# P09_F28379D-IO2.net
KiCad netlist of a schematic drawn in Altium Designer
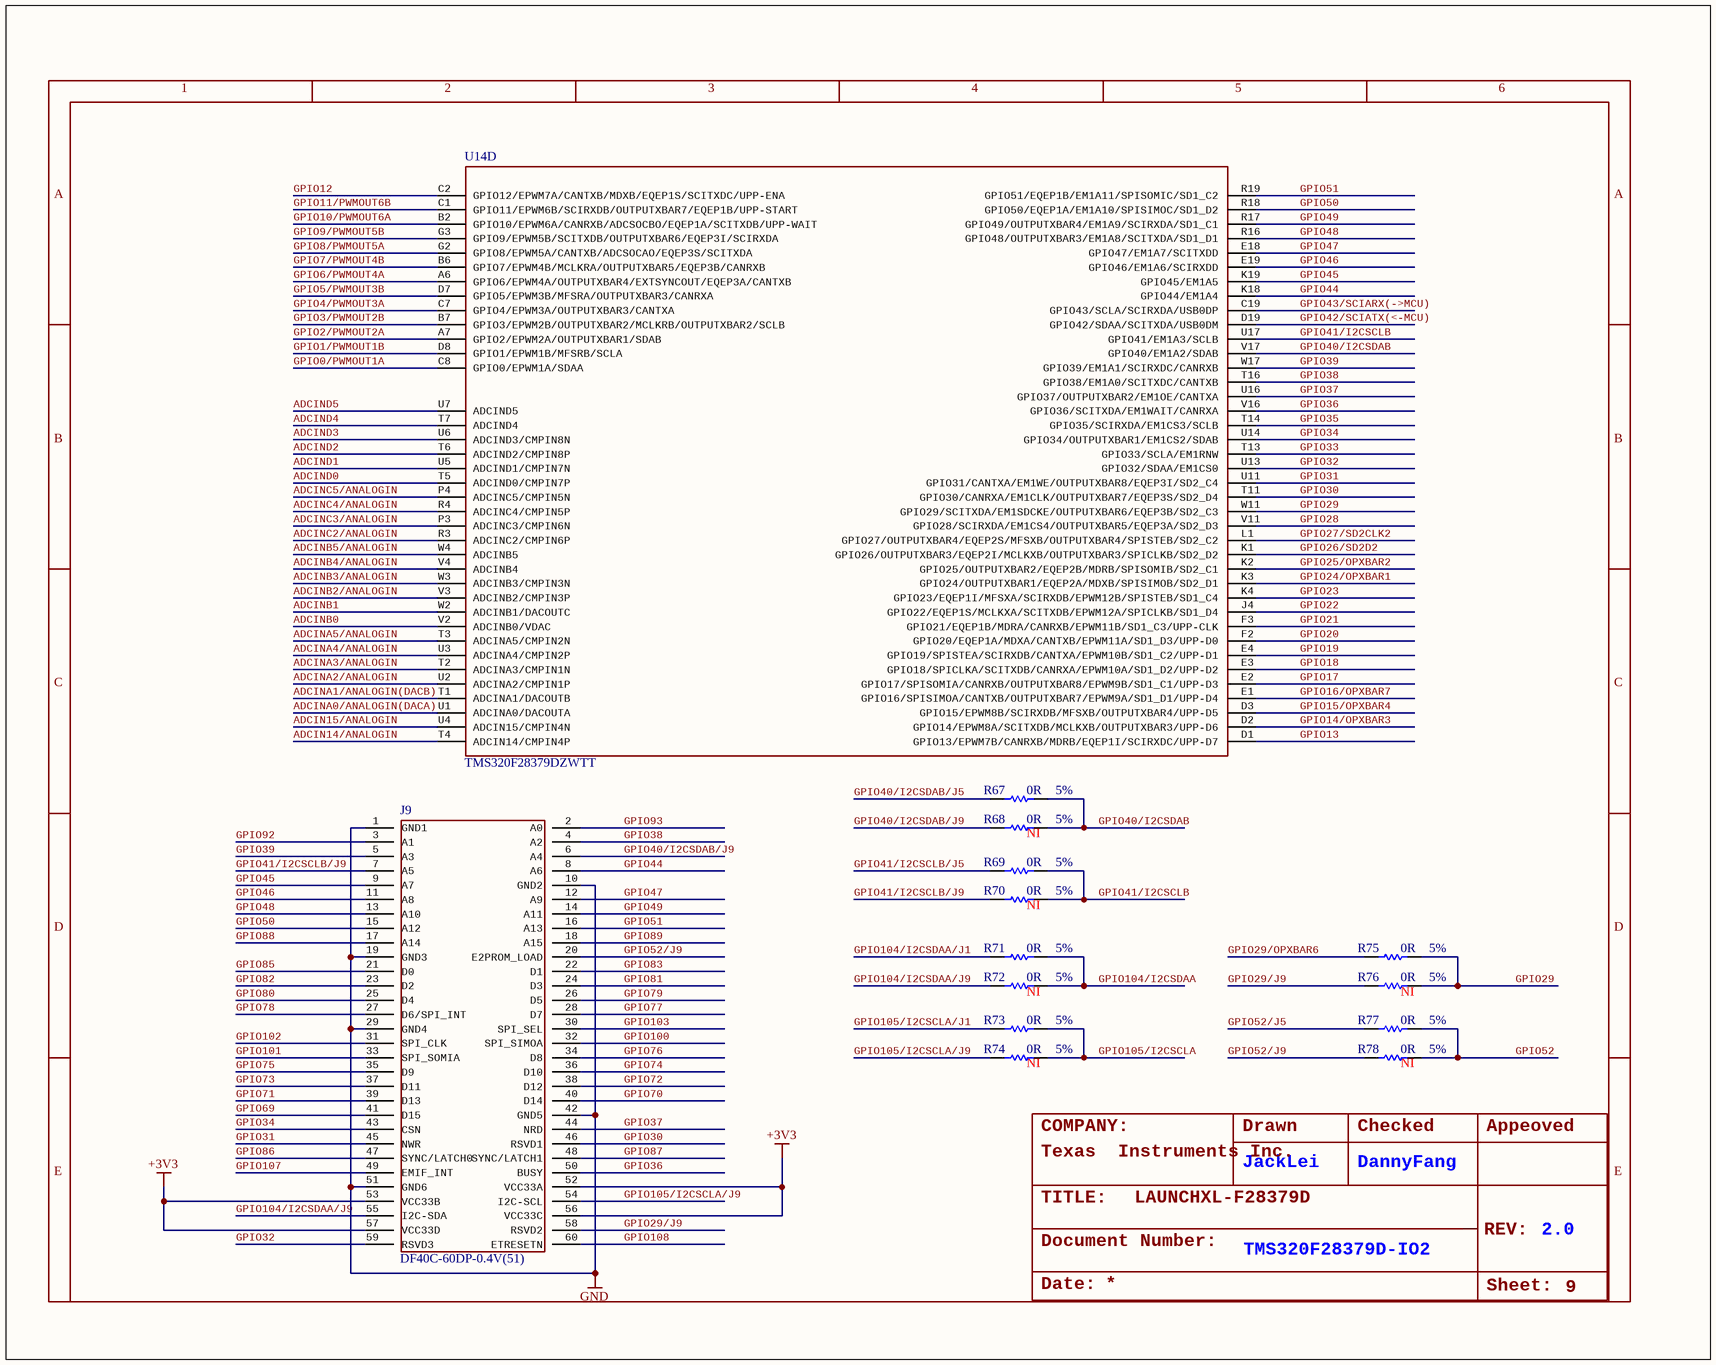
[diagram p0: P09_F28379D-IO2.SchDoc]

(export (version "E")
  (design (tool "Eeschema 10.0.6"))
  (components
    (comp (ref "J9")
      (value "DF40C-60DP-0.4V(51)")
      (footprint "BTB60P40_2X30_1152X297X114P")
      (description "CONN HDR 60POS 0.4MM SMD GOLD TR")
      (fields (field (name "MANUFACTURER") "HIROSE"))
      (libsource (lib "Embest") (part "DF40C-60DP-0.4V(51)"))
    )
    (comp (ref "R67")
      (value "0R")
      (footprint "R0603")
      (description "RES,0R,+/-5%,1/10W,SMD0603")
      (fields
        (field (name "RATING") "5%")
        (field (name "MANUFACTURER") "YAGEO")
        (field (name "MANUFACTURER PART NUMBER") "RC0603JR-070RL")
      )
      (libsource (lib "Embest") (part "R"))
    )
    (comp (ref "R68")
      (value "0R")
      (footprint "R0603")
      (description "RES,0R,+/-5%,1/10W,SMD0603")
      (fields
        (field (name "RATING") "5%")
        (field (name "ASSY") "NI")
        (field (name "MANUFACTURER") "YAGEO")
        (field (name "MANUFACTURER PART NUMBER") "RC0603JR-070RL")
      )
      (libsource (lib "Embest") (part "R"))
    )
    (comp (ref "R69")
      (value "0R")
      (footprint "R0603")
      (description "RES,0R,+/-5%,1/10W,SMD0603")
      (fields
        (field (name "RATING") "5%")
        (field (name "MANUFACTURER") "YAGEO")
        (field (name "MANUFACTURER PART NUMBER") "RC0603JR-070RL")
      )
      (libsource (lib "Embest") (part "R"))
    )
    (comp (ref "R70")
      (value "0R")
      (footprint "R0603")
      (description "RES,0R,+/-5%,1/10W,SMD0603")
      (fields
        (field (name "RATING") "5%")
        (field (name "ASSY") "NI")
        (field (name "MANUFACTURER") "YAGEO")
        (field (name "MANUFACTURER PART NUMBER") "RC0603JR-070RL")
      )
      (libsource (lib "Embest") (part "R"))
    )
    (comp (ref "R71")
      (value "0R")
      (footprint "R0603")
      (description "RES,0R,+/-5%,1/10W,SMD0603")
      (fields
        (field (name "RATING") "5%")
        (field (name "MANUFACTURER") "YAGEO")
        (field (name "MANUFACTURER PART NUMBER") "RC0603JR-070RL")
      )
      (libsource (lib "Embest") (part "R"))
    )
    (comp (ref "R72")
      (value "0R")
      (footprint "R0603")
      (description "RES,0R,+/-5%,1/10W,SMD0603")
      (fields
        (field (name "RATING") "5%")
        (field (name "ASSY") "NI")
        (field (name "MANUFACTURER") "YAGEO")
        (field (name "MANUFACTURER PART NUMBER") "RC0603JR-070RL")
      )
      (libsource (lib "Embest") (part "R"))
    )
    (comp (ref "R73")
      (value "0R")
      (footprint "R0603")
      (description "RES,0R,+/-5%,1/10W,SMD0603")
      (fields
        (field (name "RATING") "5%")
        (field (name "MANUFACTURER") "YAGEO")
        (field (name "MANUFACTURER PART NUMBER") "RC0603JR-070RL")
      )
      (libsource (lib "Embest") (part "R"))
    )
    (comp (ref "R74")
      (value "0R")
      (footprint "R0603")
      (description "RES,0R,+/-5%,1/10W,SMD0603")
      (fields
        (field (name "RATING") "5%")
        (field (name "ASSY") "NI")
        (field (name "MANUFACTURER") "YAGEO")
        (field (name "MANUFACTURER PART NUMBER") "RC0603JR-070RL")
      )
      (libsource (lib "Embest") (part "R"))
    )
    (comp (ref "R75")
      (value "0R")
      (footprint "R0603")
      (description "RES,0R,+/-5%,1/10W,SMD0603")
      (fields
        (field (name "RATING") "5%")
        (field (name "MANUFACTURER") "YAGEO")
        (field (name "MANUFACTURER PART NUMBER") "RC0603JR-070RL")
      )
      (libsource (lib "Embest") (part "R"))
    )
    (comp (ref "R76")
      (value "0R")
      (footprint "R0603")
      (description "RES,0R,+/-5%,1/10W,SMD0603")
      (fields
        (field (name "RATING") "5%")
        (field (name "ASSY") "NI")
        (field (name "MANUFACTURER") "YAGEO")
        (field (name "MANUFACTURER PART NUMBER") "RC0603JR-070RL")
      )
      (libsource (lib "Embest") (part "R"))
    )
    (comp (ref "R77")
      (value "0R")
      (footprint "R0603")
      (description "RES,0R,+/-5%,1/10W,SMD0603")
      (fields
        (field (name "RATING") "5%")
        (field (name "MANUFACTURER") "YAGEO")
        (field (name "MANUFACTURER PART NUMBER") "RC0603JR-070RL")
      )
      (libsource (lib "Embest") (part "R"))
    )
    (comp (ref "R78")
      (value "0R")
      (footprint "R0603")
      (description "RES,0R,+/-5%,1/10W,SMD0603")
      (fields
        (field (name "RATING") "5%")
        (field (name "ASSY") "NI")
        (field (name "MANUFACTURER") "YAGEO")
        (field (name "MANUFACTURER PART NUMBER") "RC0603JR-070RL")
      )
      (libsource (lib "Embest") (part "R"))
    )
    (comp (ref "U14")
      (value "TMS320F28379DZWTT")
      (footprint "BGA337C80P19X19_1600X1600X140")
      (description "IC, MCU 32BIT 1024KB,TMS320F28379DZWTT,BGA-337,SMD,customer supply")
      (fields (field (name "MANUFACTURER") "TI"))
      (libsource (lib "Embest") (part "TMS320F28379DZWTT"))
    )
  )
  (nets
    (net (code "1") (name "+3V3") (class "Default")
      (node (ref "J9") (pin "52") (pinfunction "VCC33A_52") (pintype "power_in"))
      (node (ref "J9") (pin "53") (pinfunction "VCC33B_53") (pintype "power_in"))
      (node (ref "J9") (pin "56") (pinfunction "VCC33C_56") (pintype "passive"))
      (node (ref "J9") (pin "57") (pinfunction "VCC33D_57") (pintype "passive"))
    )
    (net (code "2") (name "/ADCIN14{slash}ANALOGIN") (class "Default")
      (node (ref "U14") (pin "T4") (pinfunction "ADCIN14/CMPIN4P_T4") (pintype "passive"))
    )
    (net (code "3") (name "/ADCIN15{slash}ANALOGIN") (class "Default")
      (node (ref "U14") (pin "U4") (pinfunction "ADCIN15/CMPIN4N_U4") (pintype "passive"))
    )
    (net (code "4") (name "/ADCINA0{slash}ANALOGIN(DACA)") (class "Default")
      (node (ref "U14") (pin "U1") (pinfunction "ADCINA0/DACOUTA_U1") (pintype "passive"))
    )
    (net (code "5") (name "/ADCINA1{slash}ANALOGIN(DACB)") (class "Default")
      (node (ref "U14") (pin "T1") (pinfunction "ADCINA1/DACOUTB_T1") (pintype "passive"))
    )
    (net (code "6") (name "/ADCINA2{slash}ANALOGIN") (class "Default")
      (node (ref "U14") (pin "U2") (pinfunction "ADCINA2/CMPIN1P_U2") (pintype "passive"))
    )
    (net (code "7") (name "/ADCINA3{slash}ANALOGIN") (class "Default")
      (node (ref "U14") (pin "T2") (pinfunction "ADCINA3/CMPIN1N_T2") (pintype "passive"))
    )
    (net (code "8") (name "/ADCINA4{slash}ANALOGIN") (class "Default")
      (node (ref "U14") (pin "U3") (pinfunction "ADCINA4/CMPIN2P_U3") (pintype "passive"))
    )
    (net (code "9") (name "/ADCINA5{slash}ANALOGIN") (class "Default")
      (node (ref "U14") (pin "T3") (pinfunction "ADCINA5/CMPIN2N_T3") (pintype "passive"))
    )
    (net (code "10") (name "/ADCINB0") (class "Default")
      (node (ref "U14") (pin "V2") (pinfunction "ADCINB0/VDAC_V2") (pintype "passive"))
    )
    (net (code "11") (name "/ADCINB1") (class "Default")
      (node (ref "U14") (pin "W2") (pinfunction "ADCINB1/DACOUTC_W2") (pintype "passive"))
    )
    (net (code "12") (name "/ADCINB2{slash}ANALOGIN") (class "Default")
      (node (ref "U14") (pin "V3") (pinfunction "ADCINB2/CMPIN3P_V3") (pintype "passive"))
    )
    (net (code "13") (name "/ADCINB3{slash}ANALOGIN") (class "Default")
      (node (ref "U14") (pin "W3") (pinfunction "ADCINB3/CMPIN3N_W3") (pintype "passive"))
    )
    (net (code "14") (name "/ADCINB4{slash}ANALOGIN") (class "Default")
      (node (ref "U14") (pin "V4") (pinfunction "ADCINB4_V4") (pintype "passive"))
    )
    (net (code "15") (name "/ADCINB5{slash}ANALOGIN") (class "Default")
      (node (ref "U14") (pin "W4") (pinfunction "ADCINB5_W4") (pintype "passive"))
    )
    (net (code "16") (name "/ADCINC2{slash}ANALOGIN") (class "Default")
      (node (ref "U14") (pin "R3") (pinfunction "ADCINC2/CMPIN6P_R3") (pintype "passive"))
    )
    (net (code "17") (name "/ADCINC3{slash}ANALOGIN") (class "Default")
      (node (ref "U14") (pin "P3") (pinfunction "ADCINC3/CMPIN6N_P3") (pintype "passive"))
    )
    (net (code "18") (name "/ADCINC4{slash}ANALOGIN") (class "Default")
      (node (ref "U14") (pin "R4") (pinfunction "ADCINC4/CMPIN5P_R4") (pintype "passive"))
    )
    (net (code "19") (name "/ADCINC5{slash}ANALOGIN") (class "Default")
      (node (ref "U14") (pin "P4") (pinfunction "ADCINC5/CMPIN5N_P4") (pintype "passive"))
    )
    (net (code "20") (name "/ADCIND0") (class "Default")
      (node (ref "U14") (pin "T5") (pinfunction "ADCIND0/CMPIN7P_T5") (pintype "passive"))
    )
    (net (code "21") (name "/ADCIND1") (class "Default")
      (node (ref "U14") (pin "U5") (pinfunction "ADCIND1/CMPIN7N_U5") (pintype "passive"))
    )
    (net (code "22") (name "/ADCIND2") (class "Default")
      (node (ref "U14") (pin "T6") (pinfunction "ADCIND2/CMPIN8P_T6") (pintype "passive"))
    )
    (net (code "23") (name "/ADCIND3") (class "Default")
      (node (ref "U14") (pin "U6") (pinfunction "ADCIND3/CMPIN8N_U6") (pintype "passive"))
    )
    (net (code "24") (name "/ADCIND4") (class "Default")
      (node (ref "U14") (pin "T7") (pinfunction "ADCIND4_T7") (pintype "passive"))
    )
    (net (code "25") (name "/ADCIND5") (class "Default")
      (node (ref "U14") (pin "U7") (pinfunction "ADCIND5_U7") (pintype "passive"))
    )
    (net (code "26") (name "/GPIO0{slash}PWMOUT1A") (class "Default")
      (node (ref "U14") (pin "C8") (pinfunction "GPIO0/EPWM1A/SDAA_C8") (pintype "passive"))
    )
    (net (code "27") (name "/GPIO1{slash}PWMOUT1B") (class "Default")
      (node (ref "U14") (pin "D8") (pinfunction "GPIO1/EPWM1B/MFSRB/SCLA_D8") (pintype "passive"))
    )
    (net (code "28") (name "/GPIO2{slash}PWMOUT2A") (class "Default")
      (node (ref "U14") (pin "A7") (pinfunction "GPIO2/EPWM2A/OUTPUTXBAR1/SDAB_A7") (pintype "passive"))
    )
    (net (code "29") (name "/GPIO3{slash}PWMOUT2B") (class "Default")
      (node (ref "U14") (pin "B7") (pinfunction "GPIO3/EPWM2B/OUTPUTXBAR2/MCLKRB/OUTPUTXBAR2/SCLB_B7") (pintype "passive"))
    )
    (net (code "30") (name "/GPIO4{slash}PWMOUT3A") (class "Default")
      (node (ref "U14") (pin "C7") (pinfunction "GPIO4/EPWM3A/OUTPUTXBAR3/CANTXA_C7") (pintype "passive"))
    )
    (net (code "31") (name "/GPIO5{slash}PWMOUT3B") (class "Default")
      (node (ref "U14") (pin "D7") (pinfunction "GPIO5/EPWM3B/MFSRA/OUTPUTXBAR3/CANRXA_D7") (pintype "passive"))
    )
    (net (code "32") (name "/GPIO6{slash}PWMOUT4A") (class "Default")
      (node (ref "U14") (pin "A6") (pinfunction "GPIO6/EPWM4A/OUTPUTXBAR4/EXTSYNCOUT/EQEP3A/CANTXB_A6") (pintype "passive"))
    )
    (net (code "33") (name "/GPIO7{slash}PWMOUT4B") (class "Default")
      (node (ref "U14") (pin "B6") (pinfunction "GPIO7/EPWM4B/MCLKRA/OUTPUTXBAR5/EQEP3B/CANRXB_B6") (pintype "passive"))
    )
    (net (code "34") (name "/GPIO8{slash}PWMOUT5A") (class "Default")
      (node (ref "U14") (pin "G2") (pinfunction "GPIO8/EPWM5A/CANTXB/ADCSOCAO/EQEP3S/SCITXDA_G2") (pintype "passive"))
    )
    (net (code "35") (name "/GPIO9{slash}PWMOUT5B") (class "Default")
      (node (ref "U14") (pin "G3") (pinfunction "GPIO9/EPWM5B/SCITXDB/OUTPUTXBAR6/EQEP3I/SCIRXDA_G3") (pintype "passive"))
    )
    (net (code "36") (name "/GPIO10{slash}PWMOUT6A") (class "Default")
      (node (ref "U14") (pin "B2") (pinfunction "GPIO10/EPWM6A/CANRXB/ADCSOCBO/EQEP1A/SCITXDB/UPP-WAIT_B2") (pintype "passive"))
    )
    (net (code "37") (name "/GPIO11{slash}PWMOUT6B") (class "Default")
      (node (ref "U14") (pin "C1") (pinfunction "GPIO11/EPWM6B/SCIRXDB/OUTPUTXBAR7/EQEP1B/UPP-START_C1") (pintype "passive"))
    )
    (net (code "38") (name "/GPIO12") (class "Default")
      (node (ref "U14") (pin "C2") (pinfunction "GPIO12/EPWM7A/CANTXB/MDXB/EQEP1S/SCITXDC/UPP-ENA_C2") (pintype "passive"))
    )
    (net (code "39") (name "/GPIO13") (class "Default")
      (node (ref "U14") (pin "D1") (pinfunction "GPIO13/EPWM7B/CANRXB/MDRB/EQEP1I/SCIRXDC/UPP-D7_D1") (pintype "passive"))
    )
    (net (code "40") (name "/GPIO14{slash}OPXBAR3") (class "Default")
      (node (ref "U14") (pin "D2") (pinfunction "GPIO14/EPWM8A/SCITXDB/MCLKXB/OUTPUTXBAR3/UPP-D6_D2") (pintype "passive"))
    )
    (net (code "41") (name "/GPIO15{slash}OPXBAR4") (class "Default")
      (node (ref "U14") (pin "D3") (pinfunction "GPIO15/EPWM8B/SCIRXDB/MFSXB/OUTPUTXBAR4/UPP-D5_D3") (pintype "passive"))
    )
    (net (code "42") (name "/GPIO16{slash}OPXBAR7") (class "Default")
      (node (ref "U14") (pin "E1") (pinfunction "GPIO16/SPISIMOA/CANTXB/OUTPUTXBAR7/EPWM9A/SD1_D1/UPP-D4_E1") (pintype "passive"))
    )
    (net (code "43") (name "/GPIO17") (class "Default")
      (node (ref "U14") (pin "E2") (pinfunction "GPIO17/SPISOMIA/CANRXB/OUTPUTXBAR8/EPWM9B/SD1_C1/UPP-D3_E2") (pintype "passive"))
    )
    (net (code "44") (name "/GPIO18") (class "Default")
      (node (ref "U14") (pin "E3") (pinfunction "GPIO18/SPICLKA/SCITXDB/CANRXA/EPWM10A/SD1_D2/UPP-D2_E3") (pintype "passive"))
    )
    (net (code "45") (name "/GPIO19") (class "Default")
      (node (ref "U14") (pin "E4") (pinfunction "GPIO19/SPISTEA/SCIRXDB/CANTXA/EPWM10B/SD1_C2/UPP-D1_E4") (pintype "passive"))
    )
    (net (code "46") (name "/GPIO20") (class "Default")
      (node (ref "U14") (pin "F2") (pinfunction "GPIO20/EQEP1A/MDXA/CANTXB/EPWM11A/SD1_D3/UPP-D0_F2") (pintype "passive"))
    )
    (net (code "47") (name "/GPIO21") (class "Default")
      (node (ref "U14") (pin "F3") (pinfunction "GPIO21/EQEP1B/MDRA/CANRXB/EPWM11B/SD1_C3/UPP-CLK_F3") (pintype "passive"))
    )
    (net (code "48") (name "/GPIO22") (class "Default")
      (node (ref "U14") (pin "J4") (pinfunction "GPIO22/EQEP1S/MCLKXA/SCITXDB/EPWM12A/SPICLKB/SD1_D4_J4") (pintype "passive"))
    )
    (net (code "49") (name "/GPIO23") (class "Default")
      (node (ref "U14") (pin "K4") (pinfunction "GPIO23/EQEP1I/MFSXA/SCIRXDB/EPWM12B/SPISTEB/SD1_C4_K4") (pintype "passive"))
    )
    (net (code "50") (name "/GPIO24{slash}OPXBAR1") (class "Default")
      (node (ref "U14") (pin "K3") (pinfunction "GPIO24/OUTPUTXBAR1/EQEP2A/MDXB/SPISIMOB/SD2_D1_K3") (pintype "passive"))
    )
    (net (code "51") (name "/GPIO25{slash}OPXBAR2") (class "Default")
      (node (ref "U14") (pin "K2") (pinfunction "GPIO25/OUTPUTXBAR2/EQEP2B/MDRB/SPISOMIB/SD2_C1_K2") (pintype "passive"))
    )
    (net (code "52") (name "/GPIO26{slash}SD2D2") (class "Default")
      (node (ref "U14") (pin "K1") (pinfunction "GPIO26/OUTPUTXBAR3/EQEP2I/MCLKXB/OUTPUTXBAR3/SPICLKB/SD2_D2_K1") (pintype "passive"))
    )
    (net (code "53") (name "/GPIO27{slash}SD2CLK2") (class "Default")
      (node (ref "U14") (pin "L1") (pinfunction "GPIO27/OUTPUTXBAR4/EQEP2S/MFSXB/OUTPUTXBAR4/SPISTEB/SD2_C2_L1") (pintype "passive"))
    )
    (net (code "54") (name "/GPIO28") (class "Default")
      (node (ref "U14") (pin "V11") (pinfunction "GPIO28/SCIRXDA/EM1CS4/OUTPUTXBAR5/EQEP3A/SD2_D3_V11") (pintype "passive"))
    )
    (net (code "55") (name "/GPIO29") (class "Default")
      (node (ref "R75") (pin "1") (pinfunction "1_1") (pintype "passive"))
      (node (ref "R76") (pin "1") (pinfunction "1_1") (pintype "passive"))
      (node (ref "U14") (pin "W11") (pinfunction "GPIO29/SCITXDA/EM1SDCKE/OUTPUTXBAR6/EQEP3B/SD2_C3_W11") (pintype "passive"))
    )
    (net (code "56") (name "/GPIO29{slash}J9") (class "Default")
      (node (ref "J9") (pin "58") (pinfunction "RSVD2_58") (pintype "passive"))
      (node (ref "R76") (pin "2") (pinfunction "2_2") (pintype "passive"))
    )
    (net (code "57") (name "/GPIO29{slash}OPXBAR6") (class "Default")
      (node (ref "R75") (pin "2") (pinfunction "2_2") (pintype "passive"))
    )
    (net (code "58") (name "/GPIO30") (class "Default")
      (node (ref "J9") (pin "46") (pinfunction "RSVD1_46") (pintype "passive"))
      (node (ref "U14") (pin "T11") (pinfunction "GPIO30/CANRXA/EM1CLK/OUTPUTXBAR7/EQEP3S/SD2_D4_T11") (pintype "passive"))
    )
    (net (code "59") (name "/GPIO31") (class "Default")
      (node (ref "J9") (pin "45") (pinfunction "NWR_45") (pintype "passive"))
      (node (ref "U14") (pin "U11") (pinfunction "GPIO31/CANTXA/EM1WE/OUTPUTXBAR8/EQEP3I/SD2_C4_U11") (pintype "passive"))
    )
    (net (code "60") (name "/GPIO32") (class "Default")
      (node (ref "J9") (pin "59") (pinfunction "RSVD3_59") (pintype "passive"))
      (node (ref "U14") (pin "U13") (pinfunction "GPIO32/SDAA/EM1CS0_U13") (pintype "passive"))
    )
    (net (code "61") (name "/GPIO33") (class "Default")
      (node (ref "U14") (pin "T13") (pinfunction "GPIO33/SCLA/EM1RNW_T13") (pintype "passive"))
    )
    (net (code "62") (name "/GPIO34") (class "Default")
      (node (ref "J9") (pin "43") (pinfunction "CSN_43") (pintype "passive"))
      (node (ref "U14") (pin "U14") (pinfunction "GPIO34/OUTPUTXBAR1/EM1CS2/SDAB_U14") (pintype "passive"))
    )
    (net (code "63") (name "/GPIO35") (class "Default")
      (node (ref "U14") (pin "T14") (pinfunction "GPIO35/SCIRXDA/EM1CS3/SCLB_T14") (pintype "passive"))
    )
    (net (code "64") (name "/GPIO36") (class "Default")
      (node (ref "J9") (pin "50") (pinfunction "BUSY_50") (pintype "passive"))
      (node (ref "U14") (pin "V16") (pinfunction "GPIO36/SCITXDA/EM1WAIT/CANRXA_V16") (pintype "passive"))
    )
    (net (code "65") (name "/GPIO37") (class "Default")
      (node (ref "J9") (pin "44") (pinfunction "NRD_44") (pintype "passive"))
      (node (ref "U14") (pin "U16") (pinfunction "GPIO37/OUTPUTXBAR2/EM1OE/CANTXA_U16") (pintype "passive"))
    )
    (net (code "66") (name "/GPIO38") (class "Default")
      (node (ref "J9") (pin "4") (pinfunction "A2_4") (pintype "passive"))
      (node (ref "U14") (pin "T16") (pinfunction "GPIO38/EM1A0/SCITXDC/CANTXB_T16") (pintype "passive"))
    )
    (net (code "67") (name "/GPIO39") (class "Default")
      (node (ref "J9") (pin "5") (pinfunction "A3_5") (pintype "passive"))
      (node (ref "U14") (pin "W17") (pinfunction "GPIO39/EM1A1/SCIRXDC/CANRXB_W17") (pintype "passive"))
    )
    (net (code "68") (name "/GPIO40{slash}I2CSDAB") (class "Default")
      (node (ref "R67") (pin "1") (pinfunction "1_1") (pintype "passive"))
      (node (ref "R68") (pin "1") (pinfunction "1_1") (pintype "passive"))
      (node (ref "U14") (pin "V17") (pinfunction "GPIO40/EM1A2/SDAB_V17") (pintype "passive"))
    )
    (net (code "69") (name "/GPIO40{slash}I2CSDAB{slash}J5") (class "Default")
      (node (ref "R67") (pin "2") (pinfunction "2_2") (pintype "passive"))
    )
    (net (code "70") (name "/GPIO40{slash}I2CSDAB{slash}J9") (class "Default")
      (node (ref "J9") (pin "6") (pinfunction "A4_6") (pintype "passive"))
      (node (ref "R68") (pin "2") (pinfunction "2_2") (pintype "passive"))
    )
    (net (code "71") (name "/GPIO41{slash}I2CSCLB") (class "Default")
      (node (ref "R69") (pin "1") (pinfunction "1_1") (pintype "passive"))
      (node (ref "R70") (pin "1") (pinfunction "1_1") (pintype "passive"))
      (node (ref "U14") (pin "U17") (pinfunction "GPIO41/EM1A3/SCLB_U17") (pintype "passive"))
    )
    (net (code "72") (name "/GPIO41{slash}I2CSCLB{slash}J5") (class "Default")
      (node (ref "R69") (pin "2") (pinfunction "2_2") (pintype "passive"))
    )
    (net (code "73") (name "/GPIO41{slash}I2CSCLB{slash}J9") (class "Default")
      (node (ref "J9") (pin "7") (pinfunction "A5_7") (pintype "passive"))
      (node (ref "R70") (pin "2") (pinfunction "2_2") (pintype "passive"))
    )
    (net (code "74") (name "/GPIO42{slash}SCIATX(<-MCU)") (class "Default")
      (node (ref "U14") (pin "D19") (pinfunction "GPIO42/SDAA/SCITXDA/USB0DM_D19") (pintype "passive"))
    )
    (net (code "75") (name "/GPIO43{slash}SCIARX(->MCU)") (class "Default")
      (node (ref "U14") (pin "C19") (pinfunction "GPIO43/SCLA/SCIRXDA/USB0DP_C19") (pintype "passive"))
    )
    (net (code "76") (name "/GPIO44") (class "Default")
      (node (ref "J9") (pin "8") (pinfunction "A6_8") (pintype "passive"))
      (node (ref "U14") (pin "K18") (pinfunction "GPIO44/EM1A4_K18") (pintype "passive"))
    )
    (net (code "77") (name "/GPIO45") (class "Default")
      (node (ref "J9") (pin "9") (pinfunction "A7_9") (pintype "passive"))
      (node (ref "U14") (pin "K19") (pinfunction "GPIO45/EM1A5_K19") (pintype "passive"))
    )
    (net (code "78") (name "/GPIO46") (class "Default")
      (node (ref "J9") (pin "11") (pinfunction "A8_11") (pintype "passive"))
      (node (ref "U14") (pin "E19") (pinfunction "GPIO46/EM1A6/SCIRXDD_E19") (pintype "passive"))
    )
    (net (code "79") (name "/GPIO47") (class "Default")
      (node (ref "J9") (pin "12") (pinfunction "A9_12") (pintype "passive"))
      (node (ref "U14") (pin "E18") (pinfunction "GPIO47/EM1A7/SCITXDD_E18") (pintype "passive"))
    )
    (net (code "80") (name "/GPIO48") (class "Default")
      (node (ref "J9") (pin "13") (pinfunction "A10_13") (pintype "passive"))
      (node (ref "U14") (pin "R16") (pinfunction "GPIO48/OUTPUTXBAR3/EM1A8/SCITXDA/SD1_D1_R16") (pintype "passive"))
    )
    (net (code "81") (name "/GPIO49") (class "Default")
      (node (ref "J9") (pin "14") (pinfunction "A11_14") (pintype "passive"))
      (node (ref "U14") (pin "R17") (pinfunction "GPIO49/OUTPUTXBAR4/EM1A9/SCIRXDA/SD1_C1_R17") (pintype "passive"))
    )
    (net (code "82") (name "/GPIO50") (class "Default")
      (node (ref "J9") (pin "15") (pinfunction "A12_15") (pintype "passive"))
      (node (ref "U14") (pin "R18") (pinfunction "GPIO50/EQEP1A/EM1A10/SPISIMOC/SD1_D2_R18") (pintype "passive"))
    )
    (net (code "83") (name "/GPIO51") (class "Default")
      (node (ref "J9") (pin "16") (pinfunction "A13_16") (pintype "passive"))
      (node (ref "U14") (pin "R19") (pinfunction "GPIO51/EQEP1B/EM1A11/SPISOMIC/SD1_C2_R19") (pintype "passive"))
    )
    (net (code "84") (name "/GPIO52") (class "Default")
      (node (ref "R77") (pin "1") (pinfunction "1_1") (pintype "passive"))
      (node (ref "R78") (pin "1") (pinfunction "1_1") (pintype "passive"))
    )
    (net (code "85") (name "/GPIO52{slash}J5") (class "Default")
      (node (ref "R77") (pin "2") (pinfunction "2_2") (pintype "passive"))
    )
    (net (code "86") (name "/GPIO52{slash}J9") (class "Default")
      (node (ref "J9") (pin "20") (pinfunction "E2PROM_LOAD_20") (pintype "passive"))
      (node (ref "R78") (pin "2") (pinfunction "2_2") (pintype "passive"))
    )
    (net (code "87") (name "/GPIO69") (class "Default")
      (node (ref "J9") (pin "41") (pinfunction "D15_41") (pintype "passive"))
    )
    (net (code "88") (name "/GPIO70") (class "Default")
      (node (ref "J9") (pin "40") (pinfunction "D14_40") (pintype "passive"))
    )
    (net (code "89") (name "/GPIO71") (class "Default")
      (node (ref "J9") (pin "39") (pinfunction "D13_39") (pintype "passive"))
    )
    (net (code "90") (name "/GPIO72") (class "Default")
      (node (ref "J9") (pin "38") (pinfunction "D12_38") (pintype "passive"))
    )
    (net (code "91") (name "/GPIO73") (class "Default")
      (node (ref "J9") (pin "37") (pinfunction "D11_37") (pintype "passive"))
    )
    (net (code "92") (name "/GPIO74") (class "Default")
      (node (ref "J9") (pin "36") (pinfunction "D10_36") (pintype "passive"))
    )
    (net (code "93") (name "/GPIO75") (class "Default")
      (node (ref "J9") (pin "35") (pinfunction "D9_35") (pintype "passive"))
    )
    (net (code "94") (name "/GPIO76") (class "Default")
      (node (ref "J9") (pin "34") (pinfunction "D8_34") (pintype "passive"))
    )
    (net (code "95") (name "/GPIO77") (class "Default")
      (node (ref "J9") (pin "28") (pinfunction "D7_28") (pintype "passive"))
    )
    (net (code "96") (name "/GPIO78") (class "Default")
      (node (ref "J9") (pin "27") (pinfunction "D6/SPI_INT_27") (pintype "passive"))
    )
    (net (code "97") (name "/GPIO79") (class "Default")
      (node (ref "J9") (pin "26") (pinfunction "D5_26") (pintype "passive"))
    )
    (net (code "98") (name "/GPIO80") (class "Default")
      (node (ref "J9") (pin "25") (pinfunction "D4_25") (pintype "passive"))
    )
    (net (code "99") (name "/GPIO81") (class "Default")
      (node (ref "J9") (pin "24") (pinfunction "D3_24") (pintype "passive"))
    )
    (net (code "100") (name "/GPIO82") (class "Default")
      (node (ref "J9") (pin "23") (pinfunction "D2_23") (pintype "passive"))
    )
    (net (code "101") (name "/GPIO83") (class "Default")
      (node (ref "J9") (pin "22") (pinfunction "D1_22") (pintype "passive"))
    )
    (net (code "102") (name "/GPIO85") (class "Default")
      (node (ref "J9") (pin "21") (pinfunction "D0_21") (pintype "passive"))
    )
    (net (code "103") (name "/GPIO86") (class "Default")
      (node (ref "J9") (pin "47") (pinfunction "SYNC/LATCH0_47") (pintype "passive"))
    )
    (net (code "104") (name "/GPIO87") (class "Default")
      (node (ref "J9") (pin "48") (pinfunction "SYNC/LATCH1_48") (pintype "passive"))
    )
    (net (code "105") (name "/GPIO88") (class "Default")
      (node (ref "J9") (pin "17") (pinfunction "A14_17") (pintype "passive"))
    )
    (net (code "106") (name "/GPIO89") (class "Default")
      (node (ref "J9") (pin "18") (pinfunction "A15_18") (pintype "passive"))
    )
    (net (code "107") (name "/GPIO92") (class "Default")
      (node (ref "J9") (pin "3") (pinfunction "A1_3") (pintype "passive"))
    )
    (net (code "108") (name "/GPIO93") (class "Default")
      (node (ref "J9") (pin "2") (pinfunction "A0_2") (pintype "passive"))
    )
    (net (code "109") (name "/GPIO100") (class "Default")
      (node (ref "J9") (pin "32") (pinfunction "SPI_SIMOA_32") (pintype "passive"))
    )
    (net (code "110") (name "/GPIO101") (class "Default")
      (node (ref "J9") (pin "33") (pinfunction "SPI_SOMIA_33") (pintype "passive"))
    )
    (net (code "111") (name "/GPIO102") (class "Default")
      (node (ref "J9") (pin "31") (pinfunction "SPI_CLK_31") (pintype "passive"))
    )
    (net (code "112") (name "/GPIO103") (class "Default")
      (node (ref "J9") (pin "30") (pinfunction "SPI_SEL_30") (pintype "passive"))
    )
    (net (code "113") (name "/GPIO104{slash}I2CSDAA") (class "Default")
      (node (ref "R71") (pin "1") (pinfunction "1_1") (pintype "passive"))
      (node (ref "R72") (pin "1") (pinfunction "1_1") (pintype "passive"))
    )
    (net (code "114") (name "/GPIO104{slash}I2CSDAA{slash}J1") (class "Default")
      (node (ref "R71") (pin "2") (pinfunction "2_2") (pintype "passive"))
    )
    (net (code "115") (name "/GPIO104{slash}I2CSDAA{slash}J9") (class "Default")
      (node (ref "J9") (pin "55") (pinfunction "I2C-SDA_55") (pintype "passive"))
      (node (ref "R72") (pin "2") (pinfunction "2_2") (pintype "passive"))
    )
    (net (code "116") (name "/GPIO105{slash}I2CSCLA") (class "Default")
      (node (ref "R73") (pin "1") (pinfunction "1_1") (pintype "passive"))
      (node (ref "R74") (pin "1") (pinfunction "1_1") (pintype "passive"))
    )
    (net (code "117") (name "/GPIO105{slash}I2CSCLA{slash}J1") (class "Default")
      (node (ref "R73") (pin "2") (pinfunction "2_2") (pintype "passive"))
    )
    (net (code "118") (name "/GPIO105{slash}I2CSCLA{slash}J9") (class "Default")
      (node (ref "J9") (pin "54") (pinfunction "I2C-SCL_54") (pintype "passive"))
      (node (ref "R74") (pin "2") (pinfunction "2_2") (pintype "passive"))
    )
    (net (code "119") (name "/GPIO107") (class "Default")
      (node (ref "J9") (pin "49") (pinfunction "EMIF_INT_49") (pintype "passive"))
    )
    (net (code "120") (name "/GPIO108") (class "Default")
      (node (ref "J9") (pin "60") (pinfunction "ETRESETN_60") (pintype "passive"))
    )
    (net (code "121") (name "GND") (class "Default")
      (node (ref "J9") (pin "1") (pinfunction "GND1_1") (pintype "passive"))
      (node (ref "J9") (pin "10") (pinfunction "GND2_10") (pintype "passive"))
      (node (ref "J9") (pin "19") (pinfunction "GND3_19") (pintype "passive"))
      (node (ref "J9") (pin "29") (pinfunction "GND4_29") (pintype "passive"))
      (node (ref "J9") (pin "42") (pinfunction "GND5_42") (pintype "passive"))
      (node (ref "J9") (pin "51") (pinfunction "GND6_51") (pintype "passive"))
    )
  )
)
